# XBee2.net
KiCad netlist of a schematic drawn in EAGLE
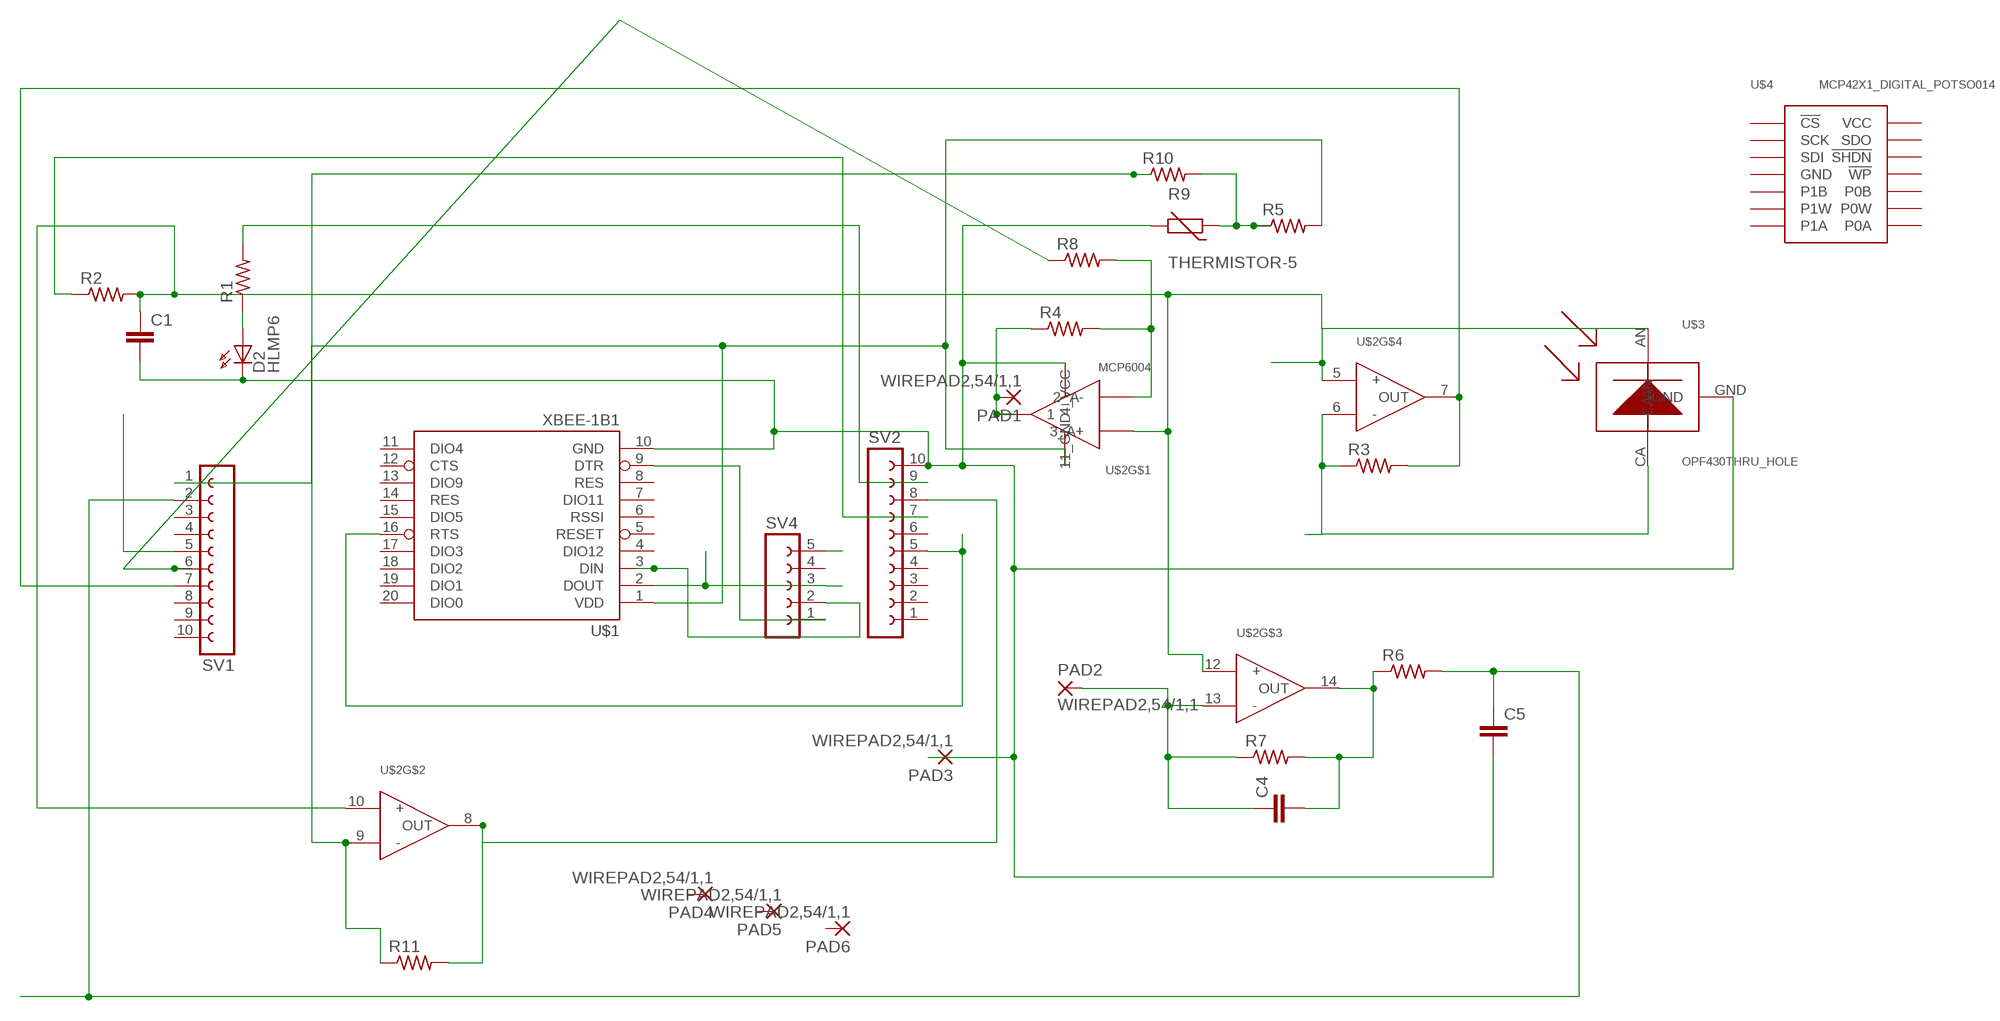
[diagram p0: schematic, sheet 1]

(export (version "E")
  (design (tool "Eeschema 10.0.6"))
  (components
    (comp (ref "C1")
      (value "C-EUC1206")
      (footprint "eagle-import:C1206")
      (libsource (lib "eagle-import") (part "C-EUC1206"))
    )
    (comp (ref "C4")
      (value "C-EUC1206")
      (footprint "eagle-import:C1206")
      (libsource (lib "eagle-import") (part "C-EUC1206"))
    )
    (comp (ref "C5")
      (value "C-EUC1206")
      (footprint "eagle-import:C1206")
      (libsource (lib "eagle-import") (part "C-EUC1206"))
    )
    (comp (ref "D2")
      (value "HLMP6")
      (footprint "eagle-import:HLMP6")
      (fields (field (name "MF") "AGILENT TECHNOLOGIES") (field (name "MPN") "HLMP-6500"))
      (libsource (lib "eagle-import") (part "HLMP6"))
    )
    (comp (ref "PAD1")
      (value "WIREPAD2,54/1,1")
      (footprint "eagle-import:2,54_1,1")
      (libsource (lib "eagle-import") (part "WIREPAD2,54/1,1"))
    )
    (comp (ref "PAD2")
      (value "WIREPAD2,54/1,1")
      (footprint "eagle-import:2,54_1,1")
      (libsource (lib "eagle-import") (part "WIREPAD2,54/1,1"))
    )
    (comp (ref "PAD3")
      (value "WIREPAD2,54/1,1")
      (footprint "eagle-import:2,54_1,1")
      (libsource (lib "eagle-import") (part "WIREPAD2,54/1,1"))
    )
    (comp (ref "PAD4")
      (value "WIREPAD2,54/1,1")
      (footprint "eagle-import:2,54_1,1")
      (libsource (lib "eagle-import") (part "WIREPAD2,54/1,1"))
    )
    (comp (ref "PAD5")
      (value "WIREPAD2,54/1,1")
      (footprint "eagle-import:2,54_1,1")
      (libsource (lib "eagle-import") (part "WIREPAD2,54/1,1"))
    )
    (comp (ref "PAD6")
      (value "WIREPAD2,54/1,1")
      (footprint "eagle-import:2,54_1,1")
      (libsource (lib "eagle-import") (part "WIREPAD2,54/1,1"))
    )
    (comp (ref "R1")
      (value "R-US_M1206")
      (footprint "eagle-import:M1206")
      (libsource (lib "eagle-import") (part "R-US_M1206"))
    )
    (comp (ref "R2")
      (value "R-US_M1206")
      (footprint "eagle-import:M1206")
      (libsource (lib "eagle-import") (part "R-US_M1206"))
    )
    (comp (ref "R3")
      (value "R-US_M1206")
      (footprint "eagle-import:M1206")
      (libsource (lib "eagle-import") (part "R-US_M1206"))
    )
    (comp (ref "R4")
      (value "R-US_M1206")
      (footprint "eagle-import:M1206")
      (libsource (lib "eagle-import") (part "R-US_M1206"))
    )
    (comp (ref "R5")
      (value "R-US_M1206")
      (footprint "eagle-import:M1206")
      (libsource (lib "eagle-import") (part "R-US_M1206"))
    )
    (comp (ref "R6")
      (value "R-US_M1206")
      (footprint "eagle-import:M1206")
      (libsource (lib "eagle-import") (part "R-US_M1206"))
    )
    (comp (ref "R7")
      (value "R-US_M1206")
      (footprint "eagle-import:M1206")
      (libsource (lib "eagle-import") (part "R-US_M1206"))
    )
    (comp (ref "R8")
      (value "R-US_M1206")
      (footprint "eagle-import:M1206")
      (libsource (lib "eagle-import") (part "R-US_M1206"))
    )
    (comp (ref "R9")
      (value "THERMISTOR-5")
      (footprint "eagle-import:R-5")
      (libsource (lib "eagle-import") (part "THERMISTOR-5"))
    )
    (comp (ref "R10")
      (value "R-US_M1206")
      (footprint "eagle-import:M1206")
      (libsource (lib "eagle-import") (part "R-US_M1206"))
    )
    (comp (ref "R11")
      (value "R-US_M1206")
      (footprint "eagle-import:M1206")
      (libsource (lib "eagle-import") (part "R-US_M1206"))
    )
    (comp (ref "SV1")
      (value "FE10-1")
      (footprint "eagle-import:FE10")
      (libsource (lib "eagle-import") (part "FE10-1"))
    )
    (comp (ref "SV2")
      (value "FE10-1")
      (footprint "eagle-import:FE10")
      (libsource (lib "eagle-import") (part "FE10-1"))
    )
    (comp (ref "SV4")
      (value "FE05-1")
      (footprint "eagle-import:FE05-1")
      (libsource (lib "eagle-import") (part "FE05-1"))
    )
    (comp (ref "U$1")
      (value "XBEE-1B1")
      (footprint "eagle-import:XBEE-1")
      (libsource (lib "eagle-import") (part "XBEE-1B1"))
    )
    (comp (ref "U$2")
      (value "MCP6004")
      (footprint "eagle-import:SO014")
      (libsource (lib "eagle-import") (part "MCP6004"))
    )
    (comp (ref "U$3")
      (value "OPF430THRU_HOLE")
      (footprint "eagle-import:OPF430")
      (libsource (lib "eagle-import") (part "OPF430THRU_HOLE"))
    )
    (comp (ref "U$4")
      (value "MCP42X1_DIGITAL_POTSO014")
      (footprint "eagle-import:SO014")
      (libsource (lib "eagle-import") (part "MCP42X1_DIGITAL_POTSO014"))
    )
  )
  (nets
    (net (code "1") (name "Net-(C5-Pad1)") (class "Default")
      (node (ref "C5") (pin "1") (pinfunction "1_1") (pintype "passive"))
      (node (ref "R6") (pin "2") (pinfunction "2_2") (pintype "passive"))
      (node (ref "SV1") (pin "2") (pinfunction "2_2") (pintype "passive"))
    )
    (net (code "2") (name "Net-(D2-PadA)") (class "Default")
      (node (ref "D2") (pin "A") (pinfunction "A_A") (pintype "passive"))
      (node (ref "R1") (pin "1") (pinfunction "1_1") (pintype "passive"))
    )
    (net (code "3") (name "Net-(PAD1-P)") (class "Default")
      (node (ref "PAD1") (pin "1") (pinfunction "P_1") (pintype "passive"))
      (node (ref "R4") (pin "1") (pinfunction "1_1") (pintype "passive"))
      (node (ref "U$2") (pin "1") (pinfunction "1_1") (pintype "bidirectional"))
    )
    (net (code "4") (name "Net-(PAD2-P)") (class "Default")
      (node (ref "C4") (pin "1") (pinfunction "1_1") (pintype "passive"))
      (node (ref "PAD2") (pin "1") (pinfunction "P_1") (pintype "passive"))
      (node (ref "R7") (pin "1") (pinfunction "1_1") (pintype "passive"))
      (node (ref "U$2") (pin "13") (pinfunction "-_13") (pintype "bidirectional"))
    )
    (net (code "5") (name "Net-(PAD3-P)") (class "Default")
      (node (ref "C1") (pin "2") (pinfunction "2_2") (pintype "passive"))
      (node (ref "C5") (pin "2") (pinfunction "2_2") (pintype "passive"))
      (node (ref "D2") (pin "K") (pinfunction "K_K") (pintype "passive"))
      (node (ref "PAD3") (pin "1") (pinfunction "P_1") (pintype "passive"))
      (node (ref "R9") (pin "2") (pinfunction "2_2") (pintype "passive"))
      (node (ref "SV2") (pin "10") (pinfunction "10_10") (pintype "passive"))
      (node (ref "U$1") (pin "10") (pinfunction "GND_10") (pintype "power_in"))
      (node (ref "U$2") (pin "11") (pinfunction "11_GND_11") (pintype "power_in"))
      (node (ref "U$3") (pin "GND") (pinfunction "GND_GND") (pintype "bidirectional"))
    )
    (net (code "6") (name "Net-(R1-Pad2)") (class "Default")
      (node (ref "R1") (pin "2") (pinfunction "2_2") (pintype "passive"))
      (node (ref "SV2") (pin "9") (pinfunction "9_9") (pintype "passive"))
    )
    (net (code "7") (name "Net-(R2-Pad1)") (class "Default")
      (node (ref "R2") (pin "1") (pinfunction "1_1") (pintype "passive"))
      (node (ref "SV2") (pin "7") (pinfunction "7_7") (pintype "passive"))
    )
    (net (code "8") (name "Net-(R8-Pad1)") (class "Default")
      (node (ref "R8") (pin "1") (pinfunction "1_1") (pintype "passive"))
      (node (ref "SV1") (pin "6") (pinfunction "6_6") (pintype "passive"))
    )
    (net (code "9") (name "Net-(R10-Pad2)") (class "Default")
      (node (ref "R10") (pin "2") (pinfunction "2_2") (pintype "passive"))
      (node (ref "R5") (pin "1") (pinfunction "1_1") (pintype "passive"))
      (node (ref "R9") (pin "1") (pinfunction "1_1") (pintype "passive"))
    )
    (net (code "10") (name "Net-(U$1-DIN)") (class "Default")
      (node (ref "SV4") (pin "2") (pinfunction "2_2") (pintype "passive"))
      (node (ref "U$1") (pin "3") (pinfunction "DIN_3") (pintype "input"))
    )
    (net (code "11") (name "Net-(U$1-DOUT)") (class "Default")
      (node (ref "SV4") (pin "3") (pinfunction "3_3") (pintype "passive"))
      (node (ref "U$1") (pin "2") (pinfunction "DOUT_2") (pintype "output"))
    )
    (net (code "12") (name "Net-(U$1-DTR)") (class "Default")
      (node (ref "SV4") (pin "1") (pinfunction "1_1") (pintype "passive"))
      (node (ref "U$1") (pin "9") (pinfunction "DTR_9") (pintype "bidirectional"))
    )
    (net (code "13") (name "Net-(U$1-RTS)") (class "Default")
      (node (ref "SV2") (pin "5") (pinfunction "5_5") (pintype "passive"))
      (node (ref "U$1") (pin "16") (pinfunction "RTS_16") (pintype "input"))
    )
    (net (code "14") (name "Net-(U$1-VDD)") (class "Default")
      (node (ref "R5") (pin "2") (pinfunction "2_2") (pintype "passive"))
      (node (ref "SV1") (pin "1") (pinfunction "1_1") (pintype "passive"))
      (node (ref "U$1") (pin "1") (pinfunction "VDD_1") (pintype "power_in"))
      (node (ref "U$2") (pin "4") (pinfunction "4_VCC_4") (pintype "power_in"))
    )
    (net (code "15") (name "Net-(U$2A-2_A-)") (class "Default")
      (node (ref "R4") (pin "2") (pinfunction "2_2") (pintype "passive"))
      (node (ref "R8") (pin "2") (pinfunction "2_2") (pintype "passive"))
      (node (ref "U$2") (pin "2") (pinfunction "2_A-_2") (pintype "bidirectional"))
    )
    (net (code "16") (name "Net-(U$2A-3_A+)") (class "Default")
      (node (ref "C1") (pin "1") (pinfunction "1_1") (pintype "passive"))
      (node (ref "R2") (pin "2") (pinfunction "2_2") (pintype "passive"))
      (node (ref "U$2") (pin "10") (pinfunction "+_10") (pintype "bidirectional"))
      (node (ref "U$2") (pin "12") (pinfunction "+_12") (pintype "bidirectional"))
      (node (ref "U$2") (pin "3") (pinfunction "3_A+_3") (pintype "bidirectional"))
      (node (ref "U$2") (pin "5") (pinfunction "+_5") (pintype "bidirectional"))
      (node (ref "U$3") (pin "AN") (pinfunction "AN_AN") (pintype "bidirectional"))
    )
    (net (code "17") (name "Net-(U$2B--)") (class "Default")
      (node (ref "R10") (pin "1") (pinfunction "1_1") (pintype "passive"))
      (node (ref "R11") (pin "1") (pinfunction "1_1") (pintype "passive"))
      (node (ref "U$2") (pin "9") (pinfunction "-_9") (pintype "bidirectional"))
    )
    (net (code "18") (name "Net-(U$2B-OUT)") (class "Default")
      (node (ref "R11") (pin "2") (pinfunction "2_2") (pintype "passive"))
      (node (ref "SV2") (pin "8") (pinfunction "8_8") (pintype "passive"))
      (node (ref "U$2") (pin "8") (pinfunction "OUT_8") (pintype "bidirectional"))
    )
    (net (code "19") (name "Net-(U$2C-OUT)") (class "Default")
      (node (ref "C4") (pin "2") (pinfunction "2_2") (pintype "passive"))
      (node (ref "R6") (pin "1") (pinfunction "1_1") (pintype "passive"))
      (node (ref "R7") (pin "2") (pinfunction "2_2") (pintype "passive"))
      (node (ref "U$2") (pin "14") (pinfunction "OUT_14") (pintype "bidirectional"))
    )
    (net (code "20") (name "Net-(U$2D--)") (class "Default")
      (node (ref "R3") (pin "1") (pinfunction "1_1") (pintype "passive"))
      (node (ref "U$2") (pin "6") (pinfunction "-_6") (pintype "bidirectional"))
      (node (ref "U$3") (pin "CA") (pinfunction "CA_CA") (pintype "bidirectional"))
    )
    (net (code "21") (name "Net-(U$2D-OUT)") (class "Default")
      (node (ref "R3") (pin "2") (pinfunction "2_2") (pintype "passive"))
      (node (ref "SV1") (pin "7") (pinfunction "7_7") (pintype "passive"))
      (node (ref "U$2") (pin "7") (pinfunction "OUT_7") (pintype "bidirectional"))
    )
    (net (code "22") (name "unconnected-(PAD4-P-Pad1)") (class "Default")
      (node (ref "PAD4") (pin "1") (pinfunction "P_1") (pintype "passive"))
    )
    (net (code "23") (name "unconnected-(PAD5-P-Pad1)") (class "Default")
      (node (ref "PAD5") (pin "1") (pinfunction "P_1") (pintype "passive"))
    )
    (net (code "24") (name "unconnected-(PAD6-P-Pad1)") (class "Default")
      (node (ref "PAD6") (pin "1") (pinfunction "P_1") (pintype "passive"))
    )
    (net (code "25") (name "unconnected-(SV1-Pad3)") (class "Default")
      (node (ref "SV1") (pin "3") (pinfunction "3_3") (pintype "passive"))
    )
    (net (code "26") (name "unconnected-(SV1-Pad4)") (class "Default")
      (node (ref "SV1") (pin "4") (pinfunction "4_4") (pintype "passive"))
    )
    (net (code "27") (name "unconnected-(SV1-Pad5)") (class "Default")
      (node (ref "SV1") (pin "5") (pinfunction "5_5") (pintype "passive"))
    )
    (net (code "28") (name "unconnected-(SV1-Pad8)") (class "Default")
      (node (ref "SV1") (pin "8") (pinfunction "8_8") (pintype "passive"))
    )
    (net (code "29") (name "unconnected-(SV1-Pad9)") (class "Default")
      (node (ref "SV1") (pin "9") (pinfunction "9_9") (pintype "passive"))
    )
    (net (code "30") (name "unconnected-(SV1-Pad10)") (class "Default")
      (node (ref "SV1") (pin "10") (pinfunction "10_10") (pintype "passive"))
    )
    (net (code "31") (name "unconnected-(SV2-Pad1)") (class "Default")
      (node (ref "SV2") (pin "1") (pinfunction "1_1") (pintype "passive"))
    )
    (net (code "32") (name "unconnected-(SV2-Pad2)") (class "Default")
      (node (ref "SV2") (pin "2") (pinfunction "2_2") (pintype "passive"))
    )
    (net (code "33") (name "unconnected-(SV2-Pad3)") (class "Default")
      (node (ref "SV2") (pin "3") (pinfunction "3_3") (pintype "passive"))
    )
    (net (code "34") (name "unconnected-(SV2-Pad4)") (class "Default")
      (node (ref "SV2") (pin "4") (pinfunction "4_4") (pintype "passive"))
    )
    (net (code "35") (name "unconnected-(SV2-Pad6)") (class "Default")
      (node (ref "SV2") (pin "6") (pinfunction "6_6") (pintype "passive"))
    )
    (net (code "36") (name "unconnected-(SV4-Pad4)") (class "Default")
      (node (ref "SV4") (pin "4") (pinfunction "4_4") (pintype "passive"))
    )
    (net (code "37") (name "unconnected-(SV4-Pad5)") (class "Default")
      (node (ref "SV4") (pin "5") (pinfunction "5_5") (pintype "passive"))
    )
    (net (code "38") (name "unconnected-(U$1-CTS-Pad12)") (class "Default")
      (node (ref "U$1") (pin "12") (pinfunction "CTS_12") (pintype "output"))
    )
    (net (code "39") (name "unconnected-(U$1-DIO0-Pad20)") (class "Default")
      (node (ref "U$1") (pin "20") (pinfunction "DIO0_20") (pintype "bidirectional"))
    )
    (net (code "40") (name "unconnected-(U$1-DIO1-Pad19)") (class "Default")
      (node (ref "U$1") (pin "19") (pinfunction "DIO1_19") (pintype "bidirectional"))
    )
    (net (code "41") (name "unconnected-(U$1-DIO2-Pad18)") (class "Default")
      (node (ref "U$1") (pin "18") (pinfunction "DIO2_18") (pintype "bidirectional"))
    )
    (net (code "42") (name "unconnected-(U$1-DIO3-Pad17)") (class "Default")
      (node (ref "U$1") (pin "17") (pinfunction "DIO3_17") (pintype "bidirectional"))
    )
    (net (code "43") (name "unconnected-(U$1-DIO4-Pad11)") (class "Default")
      (node (ref "U$1") (pin "11") (pinfunction "DIO4_11") (pintype "bidirectional"))
    )
    (net (code "44") (name "unconnected-(U$1-DIO5-Pad15)") (class "Default")
      (node (ref "U$1") (pin "15") (pinfunction "DIO5_15") (pintype "bidirectional"))
    )
    (net (code "45") (name "unconnected-(U$1-DIO9-Pad13)") (class "Default")
      (node (ref "U$1") (pin "13") (pinfunction "DIO9_13") (pintype "bidirectional"))
    )
    (net (code "46") (name "unconnected-(U$1-DIO11-Pad7)") (class "Default")
      (node (ref "U$1") (pin "7") (pinfunction "DIO11_7") (pintype "bidirectional"))
    )
    (net (code "47") (name "unconnected-(U$1-DIO12-Pad4)") (class "Default")
      (node (ref "U$1") (pin "4") (pinfunction "DIO12_4") (pintype "bidirectional"))
    )
    (net (code "48") (name "unconnected-(U$1-RES-Pad8)") (class "Default")
      (node (ref "U$1") (pin "8") (pinfunction "RES_8") (pintype "bidirectional"))
    )
    (net (code "49") (name "unconnected-(U$1-RES-Pad14)") (class "Default")
      (node (ref "U$1") (pin "14") (pinfunction "RES_14") (pintype "bidirectional"))
    )
    (net (code "50") (name "unconnected-(U$1-RESET-Pad5)") (class "Default")
      (node (ref "U$1") (pin "5") (pinfunction "RESET_5") (pintype "input"))
    )
    (net (code "51") (name "unconnected-(U$1-RSSI-Pad6)") (class "Default")
      (node (ref "U$1") (pin "6") (pinfunction "RSSI_6") (pintype "bidirectional"))
    )
    (net (code "52") (name "unconnected-(U$4-GND-PadP4)") (class "Default")
      (node (ref "U$4") (pin "P4") (pinfunction "GND_P4") (pintype "bidirectional"))
    )
    (net (code "53") (name "unconnected-(U$4-P0A-PadP8)") (class "Default")
      (node (ref "U$4") (pin "P8") (pinfunction "P0A_P8") (pintype "bidirectional"))
    )
    (net (code "54") (name "unconnected-(U$4-P0B-PadP10)") (class "Default")
      (node (ref "U$4") (pin "P10") (pinfunction "P0B_P10") (pintype "bidirectional"))
    )
    (net (code "55") (name "unconnected-(U$4-P0W-PadP9)") (class "Default")
      (node (ref "U$4") (pin "P9") (pinfunction "P0W_P9") (pintype "bidirectional"))
    )
    (net (code "56") (name "unconnected-(U$4-P1A-PadP7)") (class "Default")
      (node (ref "U$4") (pin "P7") (pinfunction "P1A_P7") (pintype "bidirectional"))
    )
    (net (code "57") (name "unconnected-(U$4-P1B-PadP5)") (class "Default")
      (node (ref "U$4") (pin "P5") (pinfunction "P1B_P5") (pintype "bidirectional"))
    )
    (net (code "58") (name "unconnected-(U$4-P1W-PadP6)") (class "Default")
      (node (ref "U$4") (pin "P6") (pinfunction "P1W_P6") (pintype "bidirectional"))
    )
    (net (code "59") (name "unconnected-(U$4-SCK-PadP2)") (class "Default")
      (node (ref "U$4") (pin "P2") (pinfunction "SCK_P2") (pintype "bidirectional"))
    )
    (net (code "60") (name "unconnected-(U$4-SDI-PadP3)") (class "Default")
      (node (ref "U$4") (pin "P3") (pinfunction "SDI_P3") (pintype "bidirectional"))
    )
    (net (code "61") (name "unconnected-(U$4-SDO-PadP13)") (class "Default")
      (node (ref "U$4") (pin "P13") (pinfunction "SDO_P13") (pintype "bidirectional"))
    )
    (net (code "62") (name "unconnected-(U$4-VCC-PadP14)") (class "Default")
      (node (ref "U$4") (pin "P14") (pinfunction "VCC_P14") (pintype "bidirectional"))
    )
    (net (code "63") (name "unconnected-(U$4-~{CS}-PadP1)") (class "Default")
      (node (ref "U$4") (pin "P1") (pinfunction "~{CS}_P1") (pintype "bidirectional"))
    )
    (net (code "64") (name "unconnected-(U$4-~{SHDN}-PadP12)") (class "Default")
      (node (ref "U$4") (pin "P12") (pinfunction "~{SHDN}_P12") (pintype "bidirectional"))
    )
    (net (code "65") (name "unconnected-(U$4-~{WP}-PadP11)") (class "Default")
      (node (ref "U$4") (pin "P11") (pinfunction "~{WP}_P11") (pintype "bidirectional"))
    )
  )
)
